# fab-slider-shield-v2_driver-only.net
KiCad netlist of a schematic drawn in EAGLE
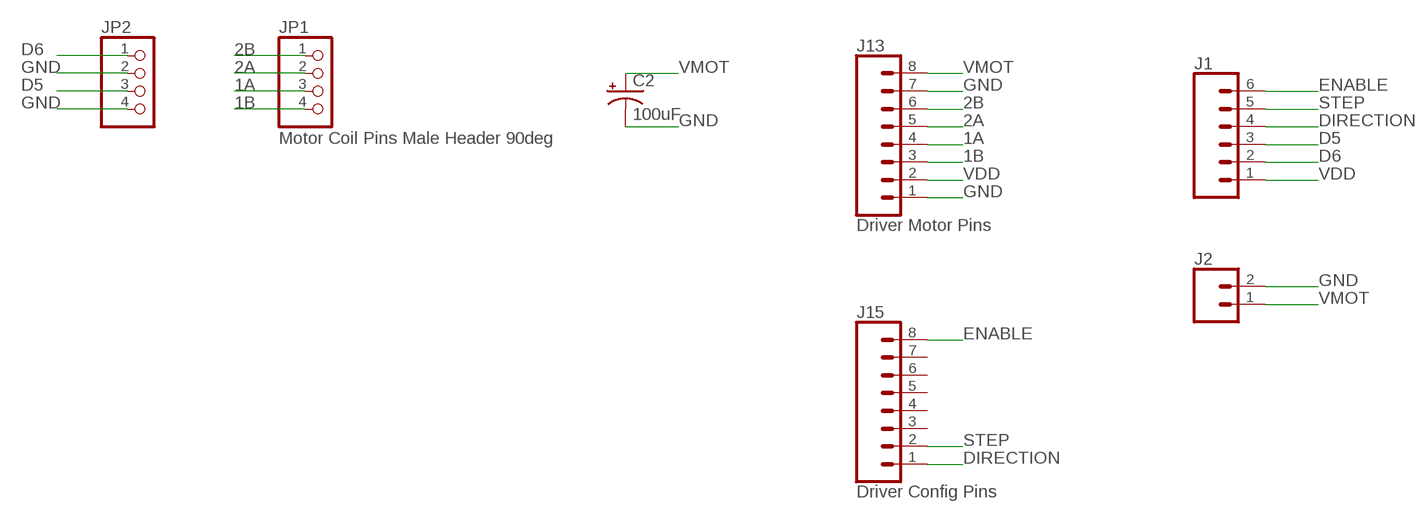
[diagram p0: schematic, sheet 1]

(export (version "E")
  (design (tool "Eeschema 10.0.6"))
  (components
    (comp (ref "C2")
      (value "100uF")
      (footprint "eagle-import:CPOL-RADIAL-2.5MM-6.5MM")
      (libsource (lib "eagle-import") (part "100UF-POLAR-RADIAL-2.5MM-25V-20%"))
    )
    (comp (ref "J1")
      (value "CONN_06LONGPADS")
      (footprint "eagle-import:1X06_LONGPADS")
      (libsource (lib "eagle-import") (part "CONN_06LONGPADS"))
    )
    (comp (ref "J2")
      (value "CONN_02PTH3")
      (footprint "eagle-import:1X02_LONGPADS")
      (libsource (lib "eagle-import") (part "CONN_02PTH3"))
    )
    (comp (ref "J13")
      (value "Driver Motor Pins")
      (footprint "eagle-import:1X08_LONGPADS")
      (libsource (lib "eagle-import") (part "CONN_08LONGPADS"))
    )
    (comp (ref "J15")
      (value "Driver Config Pins")
      (footprint "eagle-import:1X08_LONGPADS")
      (libsource (lib "eagle-import") (part "CONN_08LONGPADS"))
    )
    (comp (ref "JP1")
      (value "Motor Coil Pins Male Header 90deg")
      (footprint "eagle-import:1X04_90")
      (libsource (lib "eagle-import") (part "PINHD-1X4/90"))
    )
    (comp (ref "JP2")
      (value "PINHD-1X4/90")
      (footprint "eagle-import:1X04_90")
      (libsource (lib "eagle-import") (part "PINHD-1X4/90"))
    )
  )
  (nets
    (net (code "1") (name "/1A") (class "Default")
      (node (ref "J13") (pin "4") (pinfunction "4_4") (pintype "passive"))
      (node (ref "JP1") (pin "3") (pinfunction "3_3") (pintype "passive"))
    )
    (net (code "2") (name "/1B") (class "Default")
      (node (ref "J13") (pin "3") (pinfunction "3_3") (pintype "passive"))
      (node (ref "JP1") (pin "4") (pinfunction "4_4") (pintype "passive"))
    )
    (net (code "3") (name "/2A") (class "Default")
      (node (ref "J13") (pin "5") (pinfunction "5_5") (pintype "passive"))
      (node (ref "JP1") (pin "2") (pinfunction "2_2") (pintype "passive"))
    )
    (net (code "4") (name "/2B") (class "Default")
      (node (ref "J13") (pin "6") (pinfunction "6_6") (pintype "passive"))
      (node (ref "JP1") (pin "1") (pinfunction "1_1") (pintype "passive"))
    )
    (net (code "5") (name "/D5") (class "Default")
      (node (ref "J1") (pin "3") (pinfunction "3_3") (pintype "passive"))
      (node (ref "JP2") (pin "3") (pinfunction "3_3") (pintype "passive"))
    )
    (net (code "6") (name "/D6") (class "Default")
      (node (ref "J1") (pin "2") (pinfunction "2_2") (pintype "passive"))
      (node (ref "JP2") (pin "1") (pinfunction "1_1") (pintype "passive"))
    )
    (net (code "7") (name "/DIRECTION") (class "Default")
      (node (ref "J1") (pin "4") (pinfunction "4_4") (pintype "passive"))
      (node (ref "J15") (pin "1") (pinfunction "1_1") (pintype "passive"))
    )
    (net (code "8") (name "/ENABLE") (class "Default")
      (node (ref "J1") (pin "6") (pinfunction "6_6") (pintype "passive"))
      (node (ref "J15") (pin "8") (pinfunction "8_8") (pintype "passive"))
    )
    (net (code "9") (name "/GND") (class "Default")
      (node (ref "C2") (pin "2") (pinfunction "-_2") (pintype "passive"))
      (node (ref "J13") (pin "1") (pinfunction "1_1") (pintype "passive"))
      (node (ref "J13") (pin "7") (pinfunction "7_7") (pintype "passive"))
      (node (ref "J2") (pin "2") (pinfunction "2_2") (pintype "passive"))
      (node (ref "JP2") (pin "2") (pinfunction "2_2") (pintype "passive"))
      (node (ref "JP2") (pin "4") (pinfunction "4_4") (pintype "passive"))
    )
    (net (code "10") (name "/STEP") (class "Default")
      (node (ref "J1") (pin "5") (pinfunction "5_5") (pintype "passive"))
      (node (ref "J15") (pin "2") (pinfunction "2_2") (pintype "passive"))
    )
    (net (code "11") (name "/VDD") (class "Default")
      (node (ref "J1") (pin "1") (pinfunction "1_1") (pintype "passive"))
      (node (ref "J13") (pin "2") (pinfunction "2_2") (pintype "passive"))
    )
    (net (code "12") (name "/VMOT") (class "Default")
      (node (ref "C2") (pin "1") (pinfunction "+_1") (pintype "passive"))
      (node (ref "J13") (pin "8") (pinfunction "8_8") (pintype "passive"))
      (node (ref "J2") (pin "1") (pinfunction "1_1") (pintype "passive"))
    )
    (net (code "13") (name "unconnected-(J15-Pad3)") (class "Default")
      (node (ref "J15") (pin "3") (pinfunction "3_3") (pintype "passive"))
    )
    (net (code "14") (name "unconnected-(J15-Pad4)") (class "Default")
      (node (ref "J15") (pin "4") (pinfunction "4_4") (pintype "passive"))
    )
    (net (code "15") (name "unconnected-(J15-Pad5)") (class "Default")
      (node (ref "J15") (pin "5") (pinfunction "5_5") (pintype "passive"))
    )
    (net (code "16") (name "unconnected-(J15-Pad6)") (class "Default")
      (node (ref "J15") (pin "6") (pinfunction "6_6") (pintype "passive"))
    )
    (net (code "17") (name "unconnected-(J15-Pad7)") (class "Default")
      (node (ref "J15") (pin "7") (pinfunction "7_7") (pintype "passive"))
    )
  )
)
